# ADCS_C2Sv0_1_TopLevel.net
KiCad netlist of a schematic drawn in Altium Designer
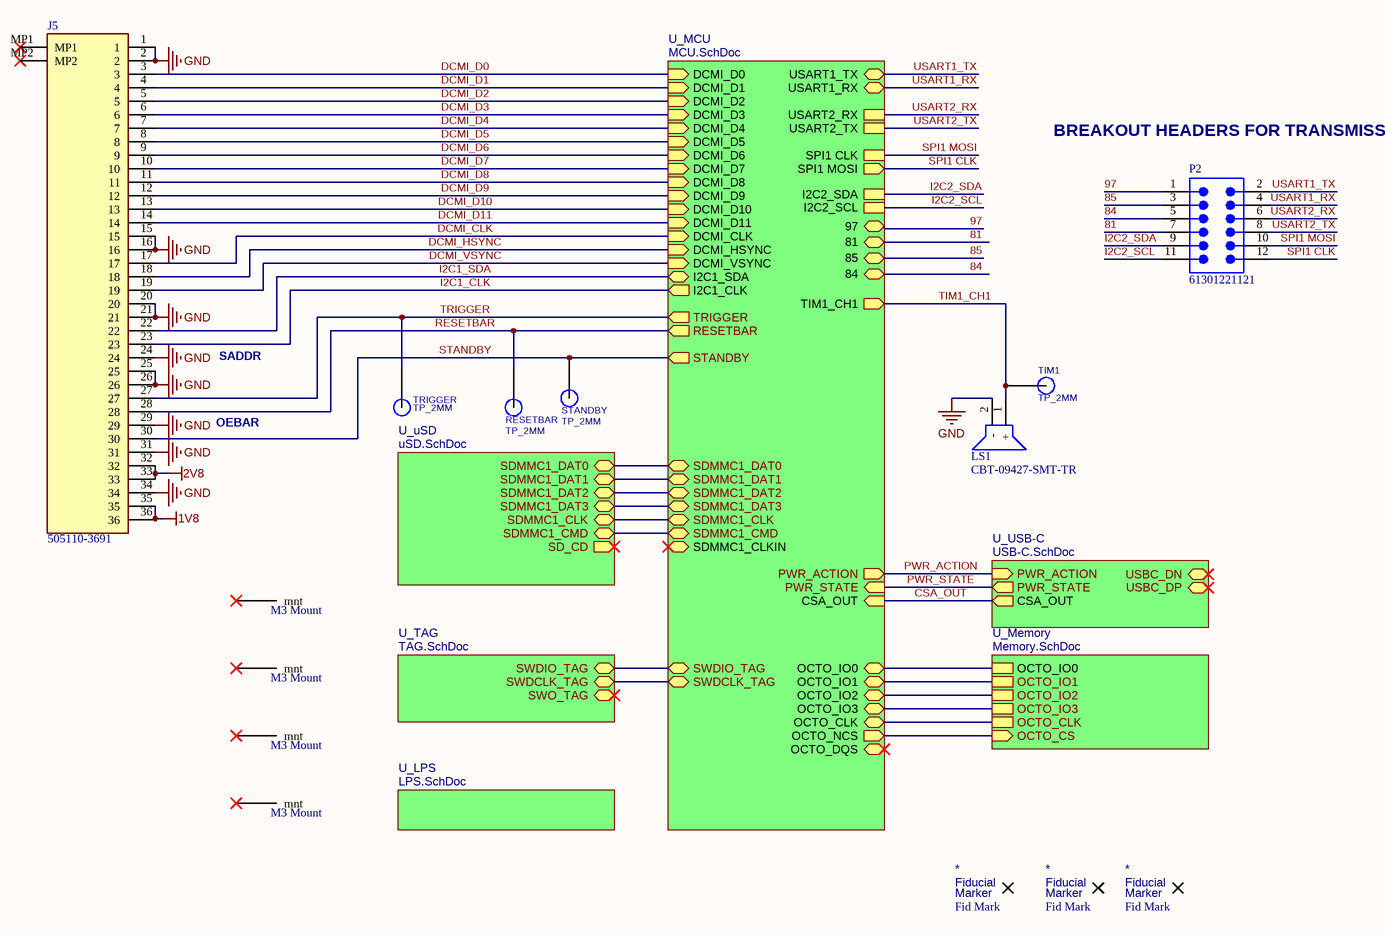
[diagram p0: ADCS C2Sv0.1_TopLevel.SchDoc]

(export (version "E")
  (design (tool "Eeschema 10.0.6"))
  (components
    (comp (ref "J5")
      (value "505110-3691")
      (footprint "C2Sv0.1:5051103691")
      (description "Connector")
      (libsource (lib "*") (part "505110-3691"))
    )
    (comp (ref "LS1")
      (value "CBT-09427-SMT-TR")
      (footprint "C2Sv0.1:CBT09427SMTTR")
      (description "Loudspeaker or Buzzer")
      (fields (field (name "MOUSER PART NUMBER") "490-CBT-09427-SMT-TR"))
      (libsource (lib "*") (part "CBT-09427-SMT-TR"))
    )
    (comp (ref "MNT1")
      (value "M3 Mount")
      (footprint "M3_Mount-Footprint-1")
      (description "M3 mounting hole")
      (fields (field (name "AUTHOR") "Raphael Ho"))
      (libsource (lib "Perth Aerospace Student Team") (part "M3_Mount-Symbol-1"))
    )
    (comp (ref "MNT2")
      (value "M3 Mount")
      (footprint "M3_Mount-Footprint-1")
      (description "M3 mounting hole")
      (fields (field (name "AUTHOR") "Raphael Ho"))
      (libsource (lib "Perth Aerospace Student Team") (part "M3_Mount-Symbol-1"))
    )
    (comp (ref "MNT3")
      (value "M3 Mount")
      (footprint "M3_Mount-Footprint-1")
      (description "M3 mounting hole")
      (fields (field (name "AUTHOR") "Raphael Ho"))
      (libsource (lib "Perth Aerospace Student Team") (part "M3_Mount-Symbol-1"))
    )
    (comp (ref "MNT4")
      (value "M3 Mount")
      (footprint "M3_Mount-Footprint-1")
      (description "M3 mounting hole")
      (fields (field (name "AUTHOR") "Raphael Ho"))
      (libsource (lib "Perth Aerospace Student Team") (part "M3_Mount-Symbol-1"))
    )
    (comp (ref "P2")
      (value "61301221121")
      (footprint "61301221121")
      (description "WR-PHD Pin Header, THT, Vertical, pitch 2.54mm, 2 Row, 12P")
      (fields (field (name "MANUFACTURER") "Wurth Elektronik"))
      (libsource (lib "Perth Aerospace Student Team") (part "621312284521"))
    )
    (comp (ref "RESETBAR")
      (value "TP_2MM")
      (footprint "TESTPOINT 2MM")
      (libsource (lib "C2S") (part "TP_2MM"))
    )
    (comp (ref "STANDBY")
      (value "TP_2MM")
      (footprint "TESTPOINT 2MM")
      (libsource (lib "C2S") (part "TP_2MM"))
    )
    (comp (ref "TIM1") (value "TP_2MM") (footprint "TESTPOINT 2MM") (libsource (lib "C2S") (part "TP_2MM")))
    (comp (ref "TRIGGER")
      (value "TP_2MM")
      (footprint "TESTPOINT 2MM")
      (libsource (lib "C2S") (part "TP_2MM"))
    )
  )
  (nets
    (net (code "1") (name "/81") (class "Default")
      (node (ref "P2") (pin "7") (pinfunction "7_7") (pintype "passive"))
    )
    (net (code "2") (name "/84") (class "Default")
      (node (ref "P2") (pin "5") (pinfunction "5_5") (pintype "passive"))
    )
    (net (code "3") (name "/85") (class "Default")
      (node (ref "P2") (pin "3") (pinfunction "3_3") (pintype "passive"))
    )
    (net (code "4") (name "/97") (class "Default")
      (node (ref "P2") (pin "1") (pinfunction "1_1") (pintype "passive"))
    )
    (net (code "6") (name "/DCMI_CLK") (class "Default")
      (node (ref "J5") (pin "17") (pinfunction "17_17") (pintype "passive"))
    )
    (net (code "7") (name "/DCMI_D0") (class "Default")
      (node (ref "J5") (pin "3") (pinfunction "3_3") (pintype "passive"))
    )
    (net (code "8") (name "/DCMI_D1") (class "Default")
      (node (ref "J5") (pin "4") (pinfunction "4_4") (pintype "passive"))
    )
    (net (code "9") (name "/DCMI_D2") (class "Default")
      (node (ref "J5") (pin "5") (pinfunction "5_5") (pintype "passive"))
    )
    (net (code "10") (name "/DCMI_D3") (class "Default")
      (node (ref "J5") (pin "6") (pinfunction "6_6") (pintype "passive"))
    )
    (net (code "11") (name "/DCMI_D4") (class "Default")
      (node (ref "J5") (pin "7") (pinfunction "7_7") (pintype "passive"))
    )
    (net (code "12") (name "/DCMI_D5") (class "Default")
      (node (ref "J5") (pin "8") (pinfunction "8_8") (pintype "passive"))
    )
    (net (code "13") (name "/DCMI_D6") (class "Default")
      (node (ref "J5") (pin "9") (pinfunction "9_9") (pintype "passive"))
    )
    (net (code "14") (name "/DCMI_D7") (class "Default")
      (node (ref "J5") (pin "10") (pinfunction "10_10") (pintype "passive"))
    )
    (net (code "15") (name "/DCMI_D8") (class "Default")
      (node (ref "J5") (pin "11") (pinfunction "11_11") (pintype "passive"))
    )
    (net (code "16") (name "/DCMI_D9") (class "Default")
      (node (ref "J5") (pin "12") (pinfunction "12_12") (pintype "passive"))
    )
    (net (code "17") (name "/DCMI_D10") (class "Default")
      (node (ref "J5") (pin "13") (pinfunction "13_13") (pintype "passive"))
    )
    (net (code "18") (name "/DCMI_D11") (class "Default")
      (node (ref "J5") (pin "14") (pinfunction "14_14") (pintype "passive"))
    )
    (net (code "19") (name "/DCMI_HSYNC") (class "Default")
      (node (ref "J5") (pin "18") (pinfunction "18_18") (pintype "passive"))
    )
    (net (code "20") (name "/DCMI_VSYNC") (class "Default")
      (node (ref "J5") (pin "19") (pinfunction "19_19") (pintype "passive"))
    )
    (net (code "21") (name "/I2C1_CLK") (class "Default")
      (node (ref "J5") (pin "23") (pinfunction "23_23") (pintype "passive"))
    )
    (net (code "22") (name "/I2C1_SDA") (class "Default")
      (node (ref "J5") (pin "22") (pinfunction "22_22") (pintype "passive"))
    )
    (net (code "23") (name "/I2C2_SCL") (class "Default")
      (node (ref "P2") (pin "11") (pinfunction "11_11") (pintype "passive"))
    )
    (net (code "24") (name "/I2C2_SDA") (class "Default")
      (node (ref "P2") (pin "9") (pinfunction "9_9") (pintype "passive"))
    )
    (net (code "34") (name "/RESETBAR") (class "Default")
      (node (ref "J5") (pin "28") (pinfunction "28_28") (pintype "passive"))
      (node (ref "RESETBAR") (pin "TP") (pinfunction "TP_2MM_TP") (pintype "passive"))
    )
    (net (code "43") (name "/SPI1 CLK") (class "Default")
      (node (ref "P2") (pin "12") (pinfunction "12_12") (pintype "passive"))
    )
    (net (code "44") (name "/SPI1 MOSI") (class "Default")
      (node (ref "P2") (pin "10") (pinfunction "10_10") (pintype "passive"))
    )
    (net (code "45") (name "/STANDBY") (class "Default")
      (node (ref "J5") (pin "30") (pinfunction "30_30") (pintype "passive"))
      (node (ref "STANDBY") (pin "TP") (pinfunction "TP_2MM_TP") (pintype "passive"))
    )
    (net (code "49") (name "/TIM1_CH1") (class "Default")
      (node (ref "LS1") (pin "1") (pinfunction "+_1") (pintype "passive"))
      (node (ref "TIM1") (pin "TP") (pinfunction "TP_2MM_TP") (pintype "passive"))
    )
    (net (code "50") (name "/TRIGGER") (class "Default")
      (node (ref "J5") (pin "27") (pinfunction "27_27") (pintype "passive"))
      (node (ref "TRIGGER") (pin "TP") (pinfunction "TP_2MM_TP") (pintype "passive"))
    )
    (net (code "51") (name "/USART1_RX") (class "Default")
      (node (ref "P2") (pin "4") (pinfunction "4_4") (pintype "passive"))
    )
    (net (code "52") (name "/USART1_TX") (class "Default")
      (node (ref "P2") (pin "2") (pinfunction "2_2") (pintype "passive"))
    )
    (net (code "53") (name "/USART2_RX") (class "Default")
      (node (ref "P2") (pin "6") (pinfunction "6_6") (pintype "passive"))
    )
    (net (code "54") (name "/USART2_TX") (class "Default")
      (node (ref "P2") (pin "8") (pinfunction "8_8") (pintype "passive"))
    )
    (net (code "57") (name "1V8") (class "Default")
      (node (ref "J5") (pin "35") (pinfunction "35_35") (pintype "passive"))
      (node (ref "J5") (pin "36") (pinfunction "36_36") (pintype "passive"))
    )
    (net (code "58") (name "2V8") (class "Default")
      (node (ref "J5") (pin "32") (pinfunction "32_32") (pintype "passive"))
      (node (ref "J5") (pin "33") (pinfunction "33_33") (pintype "passive"))
    )
    (net (code "59") (name "GND") (class "Default")
      (node (ref "J5") (pin "1") (pinfunction "1_1") (pintype "passive"))
      (node (ref "J5") (pin "15") (pinfunction "15_15") (pintype "passive"))
      (node (ref "J5") (pin "16") (pinfunction "16_16") (pintype "passive"))
      (node (ref "J5") (pin "2") (pinfunction "2_2") (pintype "passive"))
      (node (ref "J5") (pin "20") (pinfunction "20_20") (pintype "passive"))
      (node (ref "J5") (pin "21") (pinfunction "21_21") (pintype "passive"))
      (node (ref "J5") (pin "24") (pinfunction "24_24") (pintype "passive"))
      (node (ref "J5") (pin "25") (pinfunction "25_25") (pintype "passive"))
      (node (ref "J5") (pin "26") (pinfunction "26_26") (pintype "passive"))
      (node (ref "J5") (pin "29") (pinfunction "29_29") (pintype "passive"))
      (node (ref "J5") (pin "31") (pinfunction "31_31") (pintype "passive"))
      (node (ref "J5") (pin "34") (pinfunction "34_34") (pintype "passive"))
      (node (ref "LS1") (pin "2") (pinfunction "-_2") (pintype "passive"))
    )
    (net (code "60") (name "unconnected-(J5-PadMP1)") (class "Default")
      (node (ref "J5") (pin "MP1") (pinfunction "MP1_MP1") (pintype "passive+no_connect"))
    )
    (net (code "61") (name "unconnected-(J5-PadMP2)") (class "Default")
      (node (ref "J5") (pin "MP2") (pinfunction "MP2_MP2") (pintype "passive+no_connect"))
    )
    (net (code "62") (name "unconnected-(MNT1-mnt-Pad1)") (class "Default")
      (node (ref "MNT1") (pin "1") (pinfunction "mnt_1") (pintype "passive+no_connect"))
    )
    (net (code "63") (name "unconnected-(MNT2-mnt-Pad1)") (class "Default")
      (node (ref "MNT2") (pin "1") (pinfunction "mnt_1") (pintype "passive+no_connect"))
    )
    (net (code "64") (name "unconnected-(MNT3-mnt-Pad1)") (class "Default")
      (node (ref "MNT3") (pin "1") (pinfunction "mnt_1") (pintype "passive+no_connect"))
    )
    (net (code "65") (name "unconnected-(MNT4-mnt-Pad1)") (class "Default")
      (node (ref "MNT4") (pin "1") (pinfunction "mnt_1") (pintype "passive+no_connect"))
    )
  )
)
